# marlin_interface.net
KiCad netlist of a schematic drawn in EAGLE
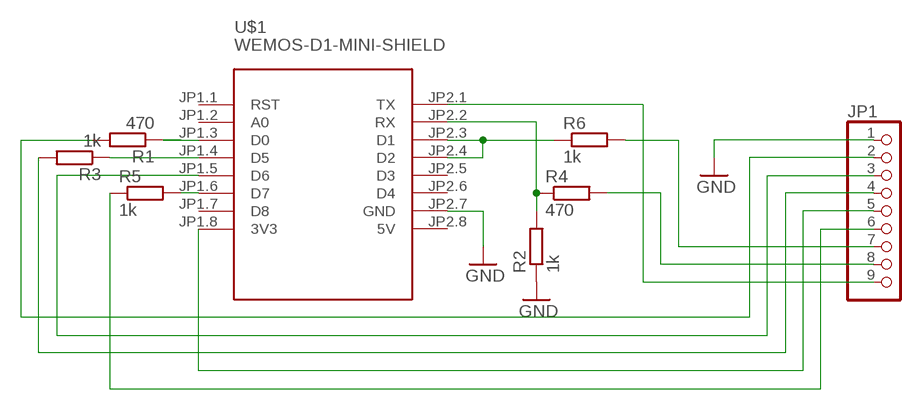
[diagram p0: schematic, sheet 1]

(export (version "E")
  (design (tool "Eeschema 10.0.6"))
  (components
    (comp (ref "JP1")
      (value "PINHD-1X9/90")
      (footprint "eagle-import:1X09_90")
      (libsource (lib "eagle-import") (part "PINHD-1X9/90"))
    )
    (comp (ref "R1")
      (value "470")
      (footprint "eagle-import:0204_5")
      (libsource (lib "eagle-import") (part "R-EU_0204/5"))
    )
    (comp (ref "R2")
      (value "1k")
      (footprint "eagle-import:0204_5")
      (libsource (lib "eagle-import") (part "R-EU_0204/5"))
    )
    (comp (ref "R3")
      (value "1k")
      (footprint "eagle-import:0204_5")
      (libsource (lib "eagle-import") (part "R-EU_0204/5"))
    )
    (comp (ref "R4")
      (value "470")
      (footprint "eagle-import:0204_5")
      (libsource (lib "eagle-import") (part "R-EU_0204/5"))
    )
    (comp (ref "R5")
      (value "1k")
      (footprint "eagle-import:0204_5")
      (libsource (lib "eagle-import") (part "R-EU_0204/5"))
    )
    (comp (ref "R6")
      (value "1k")
      (footprint "eagle-import:0204_5")
      (libsource (lib "eagle-import") (part "R-EU_0204/5"))
    )
    (comp (ref "U$1")
      (value "WEMOS-D1-MINI-SHIELD")
      (footprint "eagle-import:WEMOS-D1-MINI-SHIELD")
      (libsource (lib "eagle-import") (part "WEMOS-D1-MINI-SHIELD"))
    )
  )
  (nets
    (net (code "1") (name "/5V") (class "Default")
      (node (ref "U$1") (pin "JP2.8") (pinfunction "5V_JP2.8") (pintype "power_in"))
    )
    (net (code "2") (name "GND") (class "Default")
      (node (ref "JP1") (pin "1") (pinfunction "1_1") (pintype "passive"))
      (node (ref "R2") (pin "1") (pinfunction "1_1") (pintype "passive"))
      (node (ref "U$1") (pin "JP2.7") (pinfunction "GND_JP2.7") (pintype "power_in"))
    )
    (net (code "3") (name "Net-(JP1-Pad2)") (class "Default")
      (node (ref "JP1") (pin "2") (pinfunction "2_2") (pintype "passive"))
      (node (ref "R1") (pin "2") (pinfunction "2_2") (pintype "passive"))
    )
    (net (code "4") (name "Net-(JP1-Pad4)") (class "Default")
      (node (ref "JP1") (pin "4") (pinfunction "4_4") (pintype "passive"))
      (node (ref "R3") (pin "2") (pinfunction "2_2") (pintype "passive"))
    )
    (net (code "5") (name "Net-(JP1-Pad6)") (class "Default")
      (node (ref "JP1") (pin "6") (pinfunction "6_6") (pintype "passive"))
      (node (ref "R5") (pin "1") (pinfunction "1_1") (pintype "passive"))
    )
    (net (code "6") (name "Net-(JP1-Pad7)") (class "Default")
      (node (ref "JP1") (pin "7") (pinfunction "7_7") (pintype "passive"))
      (node (ref "R6") (pin "2") (pinfunction "2_2") (pintype "passive"))
    )
    (net (code "7") (name "Net-(JP1-Pad8)") (class "Default")
      (node (ref "JP1") (pin "8") (pinfunction "8_8") (pintype "passive"))
      (node (ref "R4") (pin "2") (pinfunction "2_2") (pintype "passive"))
    )
    (net (code "8") (name "Net-(U$1-3V3)") (class "Default")
      (node (ref "JP1") (pin "5") (pinfunction "5_5") (pintype "passive"))
      (node (ref "U$1") (pin "JP1.8") (pinfunction "3V3_JP1.8") (pintype "power_in"))
    )
    (net (code "9") (name "Net-(U$1-D0)") (class "Default")
      (node (ref "R1") (pin "1") (pinfunction "1_1") (pintype "passive"))
      (node (ref "U$1") (pin "JP1.3") (pinfunction "D0_JP1.3") (pintype "bidirectional"))
    )
    (net (code "10") (name "Net-(U$1-D1)") (class "Default")
      (node (ref "R6") (pin "1") (pinfunction "1_1") (pintype "passive"))
      (node (ref "U$1") (pin "JP2.3") (pinfunction "D1_JP2.3") (pintype "bidirectional"))
      (node (ref "U$1") (pin "JP2.4") (pinfunction "D2_JP2.4") (pintype "bidirectional"))
    )
    (net (code "11") (name "Net-(U$1-D5)") (class "Default")
      (node (ref "R3") (pin "1") (pinfunction "1_1") (pintype "passive"))
      (node (ref "U$1") (pin "JP1.4") (pinfunction "D5_JP1.4") (pintype "bidirectional"))
    )
    (net (code "12") (name "Net-(U$1-D6)") (class "Default")
      (node (ref "JP1") (pin "3") (pinfunction "3_3") (pintype "passive"))
      (node (ref "U$1") (pin "JP1.5") (pinfunction "D6_JP1.5") (pintype "bidirectional"))
    )
    (net (code "13") (name "Net-(U$1-D7)") (class "Default")
      (node (ref "R5") (pin "2") (pinfunction "2_2") (pintype "passive"))
      (node (ref "U$1") (pin "JP1.6") (pinfunction "D7_JP1.6") (pintype "bidirectional"))
    )
    (net (code "14") (name "Net-(U$1-RX)") (class "Default")
      (node (ref "R2") (pin "2") (pinfunction "2_2") (pintype "passive"))
      (node (ref "R4") (pin "1") (pinfunction "1_1") (pintype "passive"))
      (node (ref "U$1") (pin "JP2.2") (pinfunction "RX_JP2.2") (pintype "bidirectional"))
    )
    (net (code "15") (name "Net-(U$1-TX)") (class "Default")
      (node (ref "JP1") (pin "9") (pinfunction "9_9") (pintype "passive"))
      (node (ref "U$1") (pin "JP2.1") (pinfunction "TX_JP2.1") (pintype "bidirectional"))
    )
    (net (code "16") (name "unconnected-(U$1-A0-PadJP1.2)") (class "Default")
      (node (ref "U$1") (pin "JP1.2") (pinfunction "A0_JP1.2") (pintype "bidirectional"))
    )
    (net (code "17") (name "unconnected-(U$1-D3-PadJP2.5)") (class "Default")
      (node (ref "U$1") (pin "JP2.5") (pinfunction "D3_JP2.5") (pintype "bidirectional"))
    )
    (net (code "18") (name "unconnected-(U$1-D4-PadJP2.6)") (class "Default")
      (node (ref "U$1") (pin "JP2.6") (pinfunction "D4_JP2.6") (pintype "bidirectional"))
    )
    (net (code "19") (name "unconnected-(U$1-D8-PadJP1.7)") (class "Default")
      (node (ref "U$1") (pin "JP1.7") (pinfunction "D8_JP1.7") (pintype "bidirectional"))
    )
    (net (code "20") (name "unconnected-(U$1-RST-PadJP1.1)") (class "Default")
      (node (ref "U$1") (pin "JP1.1") (pinfunction "RST_JP1.1") (pintype "bidirectional"))
    )
  )
)
